# robot.net
KiCad netlist of a schematic drawn in EAGLE
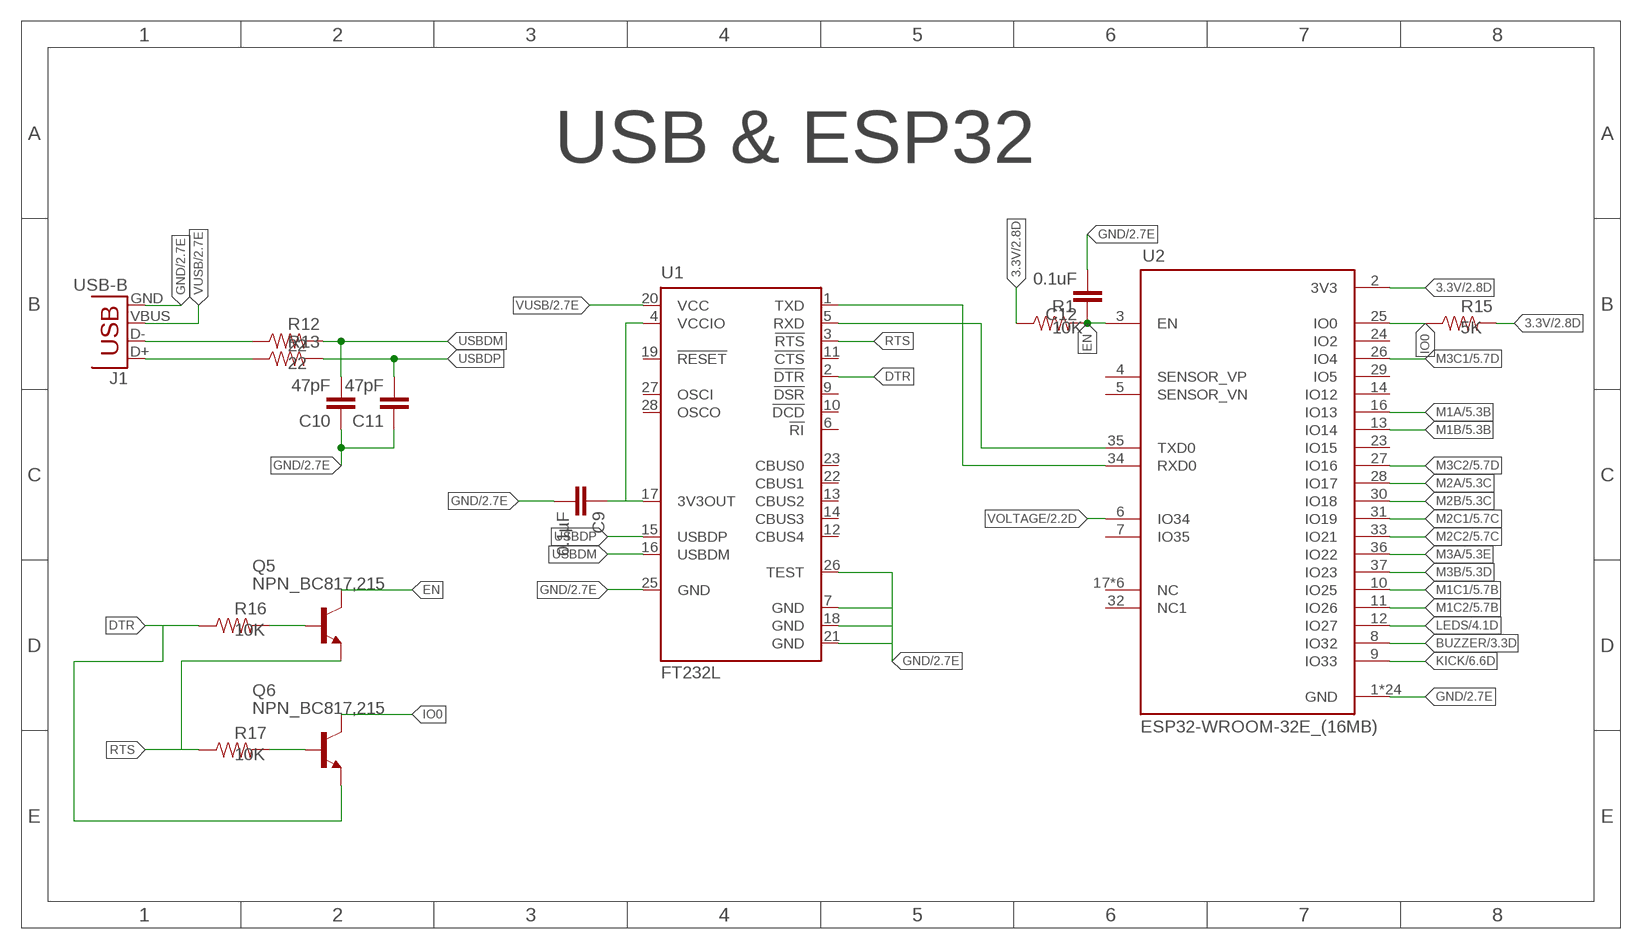
[diagram p0: schematic, sheet 1]
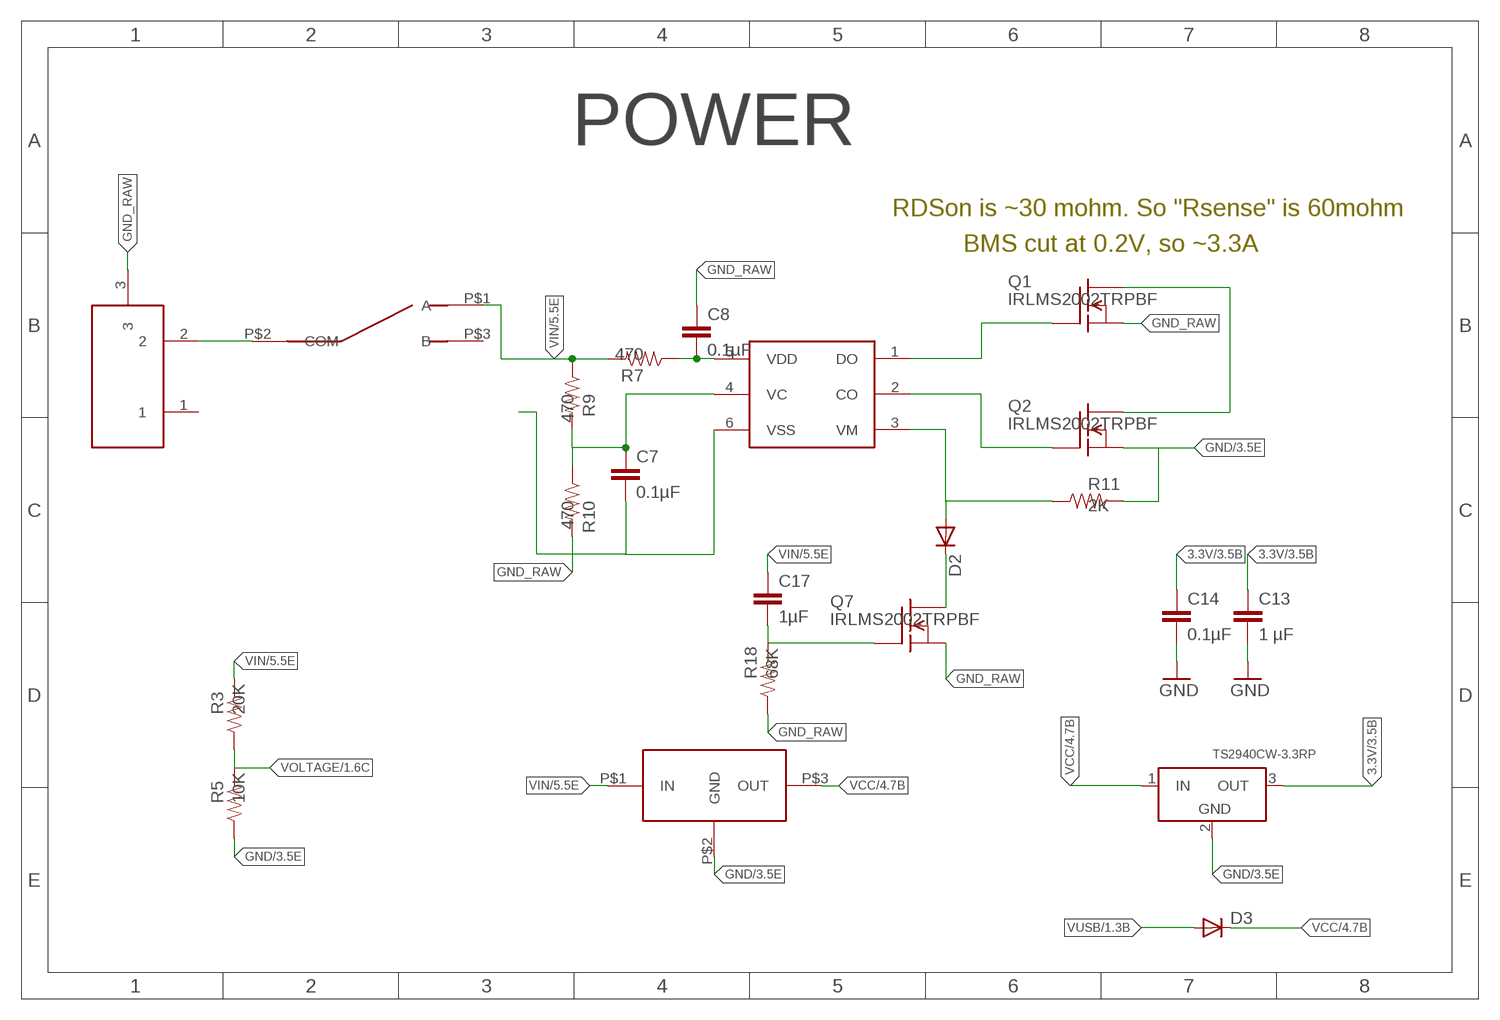
[diagram p1: schematic, sheet 2]
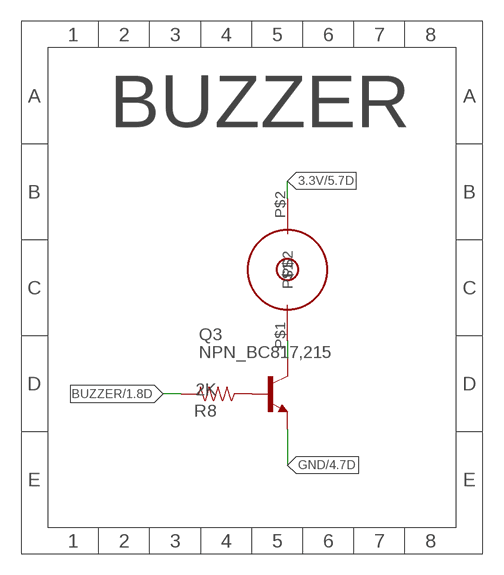
[diagram p2: schematic, sheet 3]
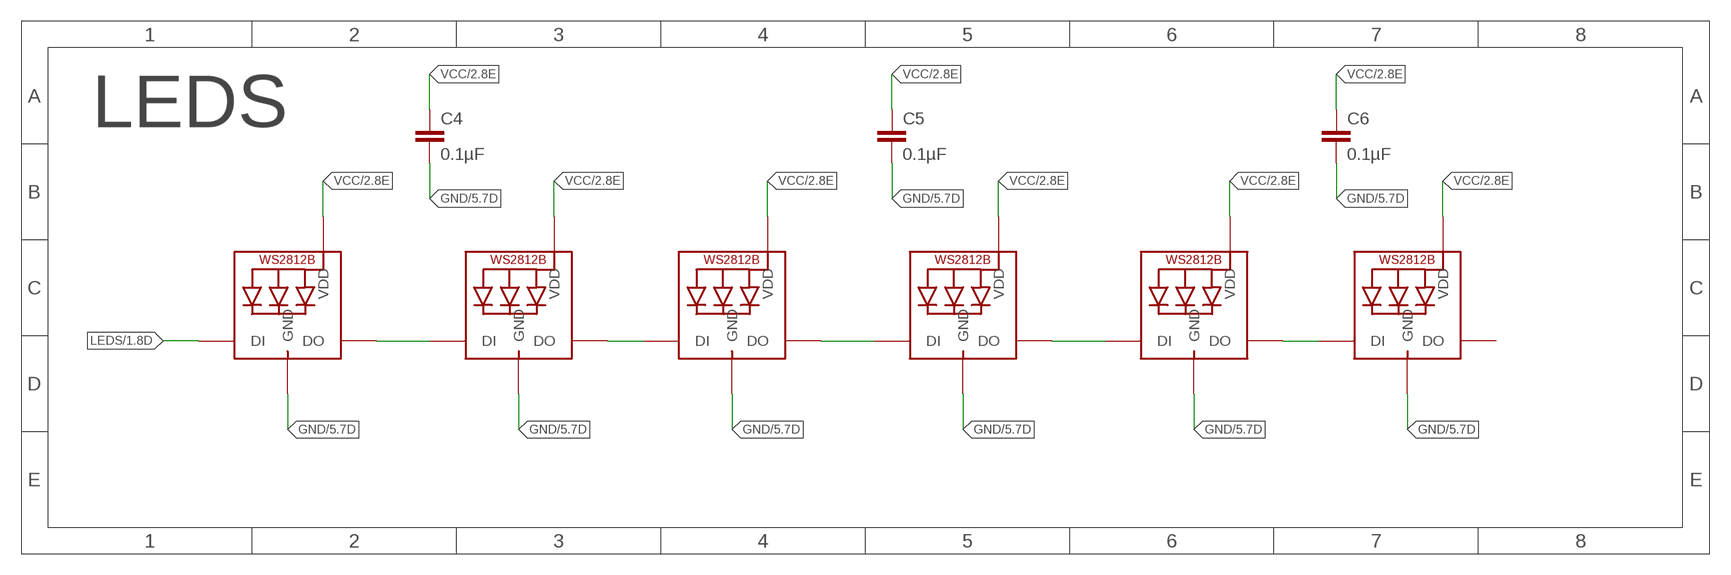
[diagram p3: schematic, sheet 4]
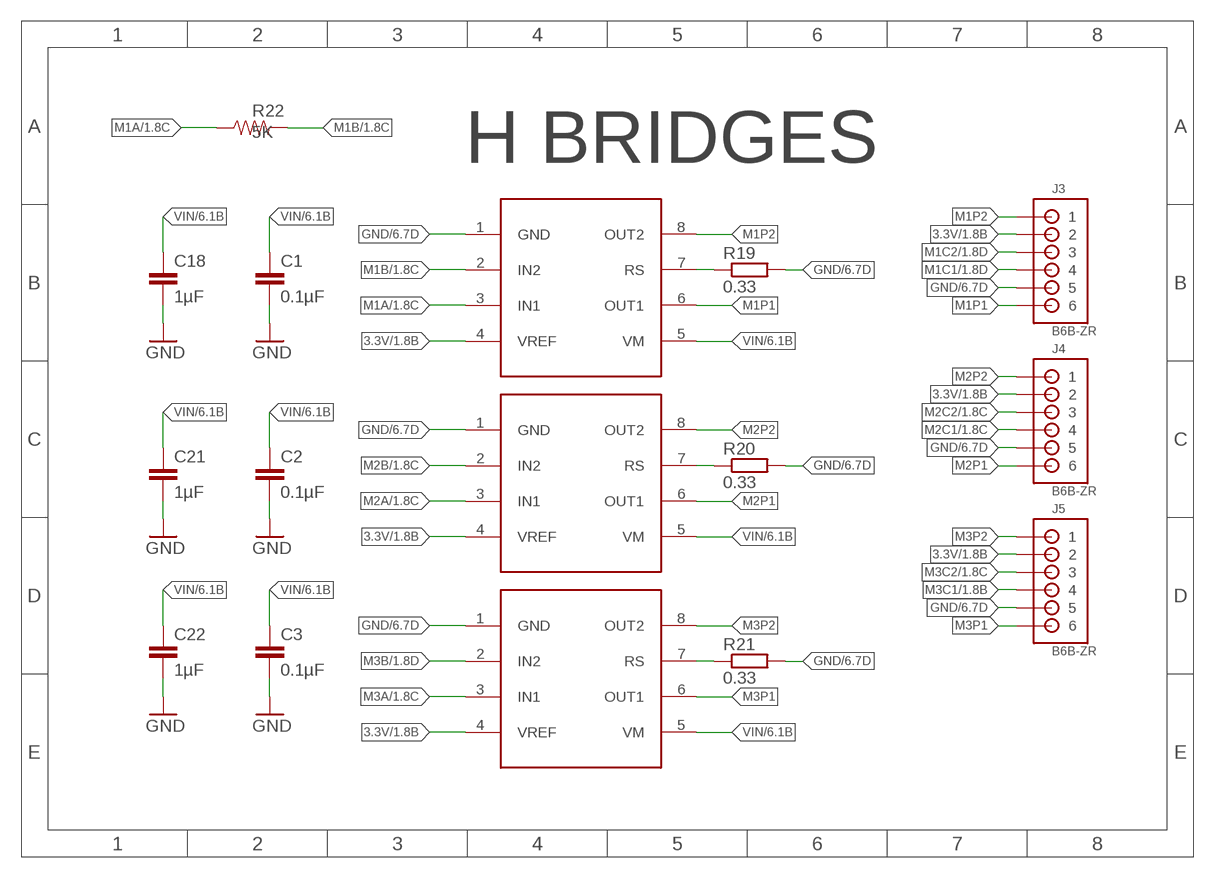
[diagram p4: schematic, sheet 5]
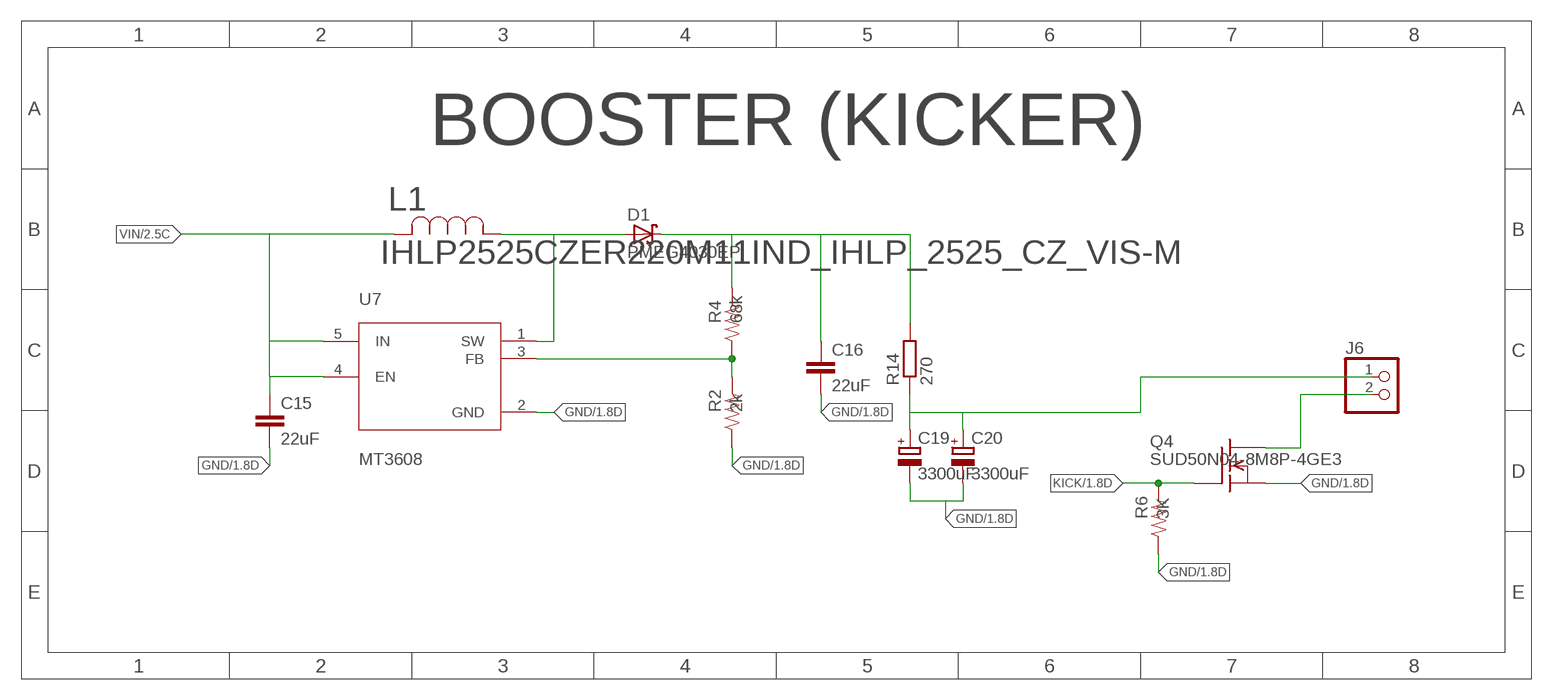
[diagram p5: schematic, sheet 6]

(export (version "E")
  (design (tool "Eeschema 10.0.6"))
  (components
    (comp (ref "C1")
      (value "0.1µF")
      (footprint "eagle-import:0805")
      (libsource (lib "eagle-import") (part "0.33UF/330NF-0805-50V-10%"))
    )
    (comp (ref "C2")
      (value "0.1µF")
      (footprint "eagle-import:0805")
      (fields (field (name "PROD_ID") "CAP-08469"))
      (libsource (lib "eagle-import") (part "0.33UF/330NF-0805-50V-10%"))
    )
    (comp (ref "C3")
      (value "0.1µF")
      (footprint "eagle-import:0805")
      (fields (field (name "PROD_ID") "CAP-08469"))
      (libsource (lib "eagle-import") (part "0.33UF/330NF-0805-50V-10%"))
    )
    (comp (ref "C18")
      (value "1µF")
      (footprint "eagle-import:0805")
      (libsource (lib "eagle-import") (part "0.33UF/330NF-0805-50V-10%"))
    )
    (comp (ref "C21")
      (value "1µF")
      (footprint "eagle-import:0805")
      (fields (field (name "PROD_ID") "CAP-08469"))
      (libsource (lib "eagle-import") (part "0.33UF/330NF-0805-50V-10%"))
    )
    (comp (ref "C22")
      (value "1µF")
      (footprint "eagle-import:0805")
      (fields (field (name "PROD_ID") "CAP-08469"))
      (libsource (lib "eagle-import") (part "0.33UF/330NF-0805-50V-10%"))
    )
    (comp (ref "J3")
      (value "B6B-ZR")
      (footprint "eagle-import:B6B-ZR")
      (libsource (lib "eagle-import") (part "B6B-ZR"))
    )
    (comp (ref "J4")
      (value "B6B-ZR")
      (footprint "eagle-import:B6B-ZR")
      (libsource (lib "eagle-import") (part "B6B-ZR"))
    )
    (comp (ref "J5")
      (value "B6B-ZR")
      (footprint "eagle-import:B6B-ZR")
      (libsource (lib "eagle-import") (part "B6B-ZR"))
    )
    (comp (ref "R19")
      (value "0.33")
      (footprint "eagle-import:R1206")
      (libsource (lib "eagle-import") (part "R-EU_R1206"))
    )
    (comp (ref "R20")
      (value "0.33")
      (footprint "eagle-import:R1206")
      (libsource (lib "eagle-import") (part "R-EU_R1206"))
    )
    (comp (ref "R21")
      (value "0.33")
      (footprint "eagle-import:R1206")
      (libsource (lib "eagle-import") (part "R-EU_R1206"))
    )
    (comp (ref "R22")
      (value "5K")
      (footprint "eagle-import:0805")
      (fields (field (name "PROD_ID") "RES-11622"))
      (libsource (lib "eagle-import") (part "0.3OHM-0805-1/8W-1%"))
    )
    (comp (ref "U10")
      (value "TB67H450FNG")
      (footprint "eagle-import:HSOP8")
      (libsource (lib "eagle-import") (part "TB67H450FNG"))
    )
    (comp (ref "U11")
      (value "TB67H450FNG")
      (footprint "eagle-import:HSOP8")
      (libsource (lib "eagle-import") (part "TB67H450FNG"))
    )
    (comp (ref "U12")
      (value "TB67H450FNG")
      (footprint "eagle-import:HSOP8")
      (libsource (lib "eagle-import") (part "TB67H450FNG"))
    )
    (comp (ref "B1")
      (value "BUZZER66")
      (footprint "eagle-import:BUZZER66")
      (libsource (lib "eagle-import") (part "BUZZER66"))
    )
    (comp (ref "Q3")
      (value "NPN_BC817,215")
      (footprint "eagle-import:SOT-23")
      (libsource (lib "eagle-import") (part "NPN_BC817,215"))
    )
    (comp (ref "R8")
      (value "2K")
      (footprint "eagle-import:0805")
      (libsource (lib "eagle-import") (part "0.3OHM-0805-1/8W-1%"))
    )
    (comp (ref "C4")
      (value "0.1µF")
      (footprint "eagle-import:0805")
      (libsource (lib "eagle-import") (part "0.33UF/330NF-0805-50V-10%"))
    )
    (comp (ref "C5")
      (value "0.1µF")
      (footprint "eagle-import:0805")
      (fields (field (name "PROD_ID") "CAP-08469"))
      (libsource (lib "eagle-import") (part "0.33UF/330NF-0805-50V-10%"))
    )
    (comp (ref "C6")
      (value "0.1µF")
      (footprint "eagle-import:0805")
      (fields (field (name "PROD_ID") "CAP-08469"))
      (libsource (lib "eagle-import") (part "0.33UF/330NF-0805-50V-10%"))
    )
    (comp (ref "LED1")
      (value "WS2812B5050")
      (footprint "eagle-import:WS2812B")
      (libsource (lib "eagle-import") (part "WS2812B5050"))
    )
    (comp (ref "LED2")
      (value "WS2812B5050")
      (footprint "eagle-import:WS2812B")
      (libsource (lib "eagle-import") (part "WS2812B5050"))
    )
    (comp (ref "LED3")
      (value "WS2812B5050")
      (footprint "eagle-import:WS2812B")
      (libsource (lib "eagle-import") (part "WS2812B5050"))
    )
    (comp (ref "LED4")
      (value "WS2812B5050")
      (footprint "eagle-import:WS2812B")
      (libsource (lib "eagle-import") (part "WS2812B5050"))
    )
    (comp (ref "LED5")
      (value "WS2812B5050")
      (footprint "eagle-import:WS2812B")
      (libsource (lib "eagle-import") (part "WS2812B5050"))
    )
    (comp (ref "LED6")
      (value "WS2812B5050")
      (footprint "eagle-import:WS2812B")
      (libsource (lib "eagle-import") (part "WS2812B5050"))
    )
    (comp (ref "C7")
      (value "0.1µF")
      (footprint "eagle-import:0805")
      (libsource (lib "eagle-import") (part "0.33UF/330NF-0805-50V-10%"))
    )
    (comp (ref "C8")
      (value "0.1µF")
      (footprint "eagle-import:0805")
      (fields (field (name "PROD_ID") "CAP-08469"))
      (libsource (lib "eagle-import") (part "0.33UF/330NF-0805-50V-10%"))
    )
    (comp (ref "C13")
      (value "1 µF")
      (footprint "eagle-import:0805")
      (fields (field (name "PROD_ID") "CAP-08469"))
      (libsource (lib "eagle-import") (part "0.33UF/330NF-0805-50V-10%"))
    )
    (comp (ref "C14")
      (value "0.1µF")
      (footprint "eagle-import:0805")
      (fields (field (name "PROD_ID") "CAP-08469"))
      (libsource (lib "eagle-import") (part "0.33UF/330NF-0805-50V-10%"))
    )
    (comp (ref "C17")
      (value "1µF")
      (footprint "eagle-import:0805")
      (fields (field (name "PROD_ID") "CAP-08469"))
      (libsource (lib "eagle-import") (part "0.33UF/330NF-0805-50V-10%"))
    )
    (comp (ref "D2")
      (value "DIODESOD")
      (footprint "eagle-import:SOD-323")
      (libsource (lib "eagle-import") (part "DIODESOD"))
    )
    (comp (ref "D3")
      (value "DIODESOD")
      (footprint "eagle-import:SOD-323")
      (libsource (lib "eagle-import") (part "DIODESOD"))
    )
    (comp (ref "J2")
      (value "DC21MMX")
      (footprint "eagle-import:DC-21MM")
      (libsource (lib "eagle-import") (part "DC21MMX"))
    )
    (comp (ref "Q1")
      (value "IRLMS2002TRPBF")
      (footprint "eagle-import:SOT23-6")
      (libsource (lib "eagle-import") (part "IRLMS2002TRPBF"))
    )
    (comp (ref "Q2")
      (value "IRLMS2002TRPBF")
      (footprint "eagle-import:SOT23-6")
      (libsource (lib "eagle-import") (part "IRLMS2002TRPBF"))
    )
    (comp (ref "Q7")
      (value "IRLMS2002TRPBF")
      (footprint "eagle-import:SOT23-6")
      (libsource (lib "eagle-import") (part "IRLMS2002TRPBF"))
    )
    (comp (ref "R3")
      (value "20K")
      (footprint "eagle-import:0805")
      (libsource (lib "eagle-import") (part "0.3OHM-0805-1/8W-1%"))
    )
    (comp (ref "R5")
      (value "10K")
      (footprint "eagle-import:0805")
      (libsource (lib "eagle-import") (part "0.3OHM-0805-1/8W-1%"))
    )
    (comp (ref "R7")
      (value "470")
      (footprint "eagle-import:0805")
      (libsource (lib "eagle-import") (part "0.3OHM-0805-1/8W-1%"))
    )
    (comp (ref "R9")
      (value "470")
      (footprint "eagle-import:0805")
      (libsource (lib "eagle-import") (part "0.3OHM-0805-1/8W-1%"))
    )
    (comp (ref "R10")
      (value "470")
      (footprint "eagle-import:0805")
      (libsource (lib "eagle-import") (part "0.3OHM-0805-1/8W-1%"))
    )
    (comp (ref "R11")
      (value "2K")
      (footprint "eagle-import:0805")
      (libsource (lib "eagle-import") (part "0.3OHM-0805-1/8W-1%"))
    )
    (comp (ref "R18")
      (value "68K")
      (footprint "eagle-import:0805")
      (fields (field (name "PROD_ID") "RES-11622"))
      (libsource (lib "eagle-import") (part "0.3OHM-0805-1/8W-1%"))
    )
    (comp (ref "REG1")
      (value "REG_5V")
      (footprint "eagle-import:TRACOPOWER")
      (libsource (lib "eagle-import") (part "REG_5V"))
    )
    (comp (ref "SW1")
      (value "L102011ML04Q")
      (footprint "eagle-import:L102011ML04Q")
      (libsource (lib "eagle-import") (part "L102011ML04Q"))
    )
    (comp (ref "U3")
      (value "S8252")
      (footprint "eagle-import:SOT23-6")
      (libsource (lib "eagle-import") (part "S8252"))
    )
    (comp (ref "U8")
      (value "TS2940CW-3.3RP")
      (footprint "eagle-import:SOT223")
      (libsource (lib "eagle-import") (part "TS2940CW-3.3RP"))
    )
    (comp (ref "C9")
      (value "0.1µF")
      (footprint "eagle-import:0805")
      (libsource (lib "eagle-import") (part "0.33UF/330NF-0805-50V-10%"))
    )
    (comp (ref "C10")
      (value "47pF")
      (footprint "eagle-import:0805")
      (libsource (lib "eagle-import") (part "CAP0805"))
    )
    (comp (ref "C11")
      (value "47pF")
      (footprint "eagle-import:0805")
      (libsource (lib "eagle-import") (part "CAP0805"))
    )
    (comp (ref "C12")
      (value "0.1uF")
      (footprint "eagle-import:0805")
      (libsource (lib "eagle-import") (part "CAP0805"))
    )
    (comp (ref "J1")
      (value "USB-B")
      (footprint "eagle-import:USB-B-PTH")
      (libsource (lib "eagle-import") (part "USBPTH"))
    )
    (comp (ref "Q5")
      (value "NPN_BC817,215")
      (footprint "eagle-import:SOT-23")
      (libsource (lib "eagle-import") (part "NPN_BC817,215"))
    )
    (comp (ref "Q6")
      (value "NPN_BC817,215")
      (footprint "eagle-import:SOT-23")
      (libsource (lib "eagle-import") (part "NPN_BC817,215"))
    )
    (comp (ref "R1")
      (value "10K")
      (footprint "eagle-import:0805")
      (fields (field (name "PROD_ID") "RES-11622"))
      (libsource (lib "eagle-import") (part "0.3OHM-0805-1/8W-1%"))
    )
    (comp (ref "R12")
      (value "22")
      (footprint "eagle-import:0805")
      (libsource (lib "eagle-import") (part "0.3OHM-0805-1/8W-1%"))
    )
    (comp (ref "R13")
      (value "22")
      (footprint "eagle-import:0805")
      (fields (field (name "PROD_ID") "RES-11622"))
      (libsource (lib "eagle-import") (part "0.3OHM-0805-1/8W-1%"))
    )
    (comp (ref "R15")
      (value "5K")
      (footprint "eagle-import:0805")
      (fields (field (name "PROD_ID") "RES-11622"))
      (libsource (lib "eagle-import") (part "0.3OHM-0805-1/8W-1%"))
    )
    (comp (ref "R16")
      (value "10K")
      (footprint "eagle-import:0805")
      (fields (field (name "PROD_ID") "RES-11622"))
      (libsource (lib "eagle-import") (part "0.3OHM-0805-1/8W-1%"))
    )
    (comp (ref "R17")
      (value "10K")
      (footprint "eagle-import:0805")
      (fields (field (name "PROD_ID") "RES-11622"))
      (libsource (lib "eagle-import") (part "0.3OHM-0805-1/8W-1%"))
    )
    (comp (ref "U1")
      (value "FT232L")
      (footprint "eagle-import:SSOP28")
      (fields (field (name "MPN") "FT232RL"))
      (libsource (lib "eagle-import") (part "FT232L"))
    )
    (comp (ref "U2")
      (value "ESP32-WROOM-32E_(16MB)")
      (footprint "eagle-import:MODULE_ESP32-WROOM-32E_(16MB)")
      (fields (field (name "MF") "Espressif Systems") (field (name "MP") "ESP32-WROOM-32E (16MB)"))
      (libsource (lib "eagle-import") (part "ESP32-WROOM-32E_(16MB)"))
    )
    (comp (ref "C15")
      (value "22uF")
      (footprint "eagle-import:C0805")
      (libsource (lib "eagle-import") (part "C-EUC0805"))
    )
    (comp (ref "C16")
      (value "22uF")
      (footprint "eagle-import:C0805")
      (libsource (lib "eagle-import") (part "C-EUC0805"))
    )
    (comp (ref "C19")
      (value "3300uF")
      (footprint "eagle-import:E5-13")
      (libsource (lib "eagle-import") (part "CPOL-EUE5-13"))
    )
    (comp (ref "C20")
      (value "3300uF")
      (footprint "eagle-import:E5-13")
      (libsource (lib "eagle-import") (part "CPOL-EUE5-13"))
    )
    (comp (ref "D1")
      (value "PMEG4030EP")
      (footprint "eagle-import:SOD128")
      (libsource (lib "eagle-import") (part "PMEG4030EP"))
    )
    (comp (ref "J6")
      (value "KICKER")
      (footprint "eagle-import:KICKER")
      (libsource (lib "eagle-import") (part "KICKER"))
    )
    (comp (ref "L1")
      (value "IHLP2525CZER220M11IND_IHLP_2525_CZ_VIS-M")
      (footprint "eagle-import:IND_IHLP_2525_CZ_VIS-M")
      (fields (field (name "MANUFACTURER_PART_NUMBER") "IHLP2525CZER220M11"))
      (libsource (lib "eagle-import") (part "IHLP2525CZER220M11IND_IHLP_2525_CZ_VIS-M"))
    )
    (comp (ref "Q4")
      (value "SUD50N04-8M8P-4GE3")
      (footprint "eagle-import:TO252")
      (libsource (lib "eagle-import") (part "SUD50N04-8M8P-4GE3"))
    )
    (comp (ref "R2")
      (value "2k")
      (footprint "eagle-import:0805")
      (libsource (lib "eagle-import") (part "0.3OHM-0805-1/8W-1%"))
    )
    (comp (ref "R4")
      (value "68k")
      (footprint "eagle-import:0805")
      (libsource (lib "eagle-import") (part "0.3OHM-0805-1/8W-1%"))
    )
    (comp (ref "R6")
      (value "3K")
      (footprint "eagle-import:0805")
      (fields (field (name "PROD_ID") "RES-11622"))
      (libsource (lib "eagle-import") (part "0.3OHM-0805-1/8W-1%"))
    )
    (comp (ref "R14")
      (value "270")
      (footprint "eagle-import:R2010")
      (libsource (lib "eagle-import") (part "R-EU_R2010"))
    )
    (comp (ref "U7")
      (value "MT3608")
      (footprint "eagle-import:SOT95P280X145-6N")
      (fields (field (name "MF") "Aerosemi Technology Co., Ltd"))
      (libsource (lib "eagle-import") (part "MT3608"))
    )
  )
  (nets
    (net (code "1") (name "1") (class "Default")
      (node (ref "J2") (pin "1") (pinfunction "1_1") (pintype "power_in"))
    )
    (net (code "2") (name "3.3V") (class "Default")
      (node (ref "B1") (pin "P$2") (pinfunction "P$2_P$2") (pintype "bidirectional"))
      (node (ref "C13") (pin "1") (pinfunction "1_1") (pintype "passive"))
      (node (ref "C14") (pin "1") (pinfunction "1_1") (pintype "passive"))
      (node (ref "J3") (pin "2") (pinfunction "2_2") (pintype "bidirectional"))
      (node (ref "J4") (pin "2") (pinfunction "2_2") (pintype "bidirectional"))
      (node (ref "J5") (pin "2") (pinfunction "2_2") (pintype "bidirectional"))
      (node (ref "R1") (pin "1") (pinfunction "1_1") (pintype "passive"))
      (node (ref "R15") (pin "2") (pinfunction "2_2") (pintype "passive"))
      (node (ref "U10") (pin "4") (pinfunction "VREF_4") (pintype "bidirectional"))
      (node (ref "U11") (pin "4") (pinfunction "VREF_4") (pintype "bidirectional"))
      (node (ref "U12") (pin "4") (pinfunction "VREF_4") (pintype "bidirectional"))
      (node (ref "U2") (pin "2") (pinfunction "3V3_2") (pintype "power_in"))
      (node (ref "U8") (pin "3") (pinfunction "OUT_3") (pintype "output"))
    )
    (net (code "3") (name "BUZZER") (class "Default")
      (node (ref "R8") (pin "2") (pinfunction "2_2") (pintype "passive"))
      (node (ref "U2") (pin "8") (pinfunction "IO32_8") (pintype "bidirectional"))
    )
    (net (code "4") (name "DTR") (class "Default")
      (node (ref "Q6") (pin "2") (pinfunction "E_2") (pintype "passive"))
      (node (ref "R16") (pin "1") (pinfunction "1_1") (pintype "passive"))
      (node (ref "U1") (pin "2") (pinfunction "~{DTR}_2") (pintype "output"))
    )
    (net (code "5") (name "EN") (class "Default")
      (node (ref "C12") (pin "1") (pinfunction "1_1") (pintype "passive"))
      (node (ref "Q5") (pin "3") (pinfunction "C_3") (pintype "passive"))
      (node (ref "R1") (pin "2") (pinfunction "2_2") (pintype "passive"))
      (node (ref "U2") (pin "3") (pinfunction "EN_3") (pintype "input"))
    )
    (net (code "6") (name "GND") (class "Default")
      (node (ref "C1") (pin "2") (pinfunction "2_2") (pintype "passive"))
      (node (ref "C10") (pin "1") (pinfunction "1_1") (pintype "passive"))
      (node (ref "C11") (pin "1") (pinfunction "1_1") (pintype "passive"))
      (node (ref "C12") (pin "2") (pinfunction "2_2") (pintype "passive"))
      (node (ref "C13") (pin "2") (pinfunction "2_2") (pintype "passive"))
      (node (ref "C14") (pin "2") (pinfunction "2_2") (pintype "passive"))
      (node (ref "C15") (pin "2") (pinfunction "2_2") (pintype "passive"))
      (node (ref "C16") (pin "2") (pinfunction "2_2") (pintype "passive"))
      (node (ref "C18") (pin "2") (pinfunction "2_2") (pintype "passive"))
      (node (ref "C19") (pin "-") (pinfunction "-_-") (pintype "passive"))
      (node (ref "C2") (pin "2") (pinfunction "2_2") (pintype "passive"))
      (node (ref "C20") (pin "-") (pinfunction "-_-") (pintype "passive"))
      (node (ref "C21") (pin "2") (pinfunction "2_2") (pintype "passive"))
      (node (ref "C22") (pin "2") (pinfunction "2_2") (pintype "passive"))
      (node (ref "C3") (pin "2") (pinfunction "2_2") (pintype "passive"))
      (node (ref "C4") (pin "2") (pinfunction "2_2") (pintype "passive"))
      (node (ref "C5") (pin "2") (pinfunction "2_2") (pintype "passive"))
      (node (ref "C6") (pin "2") (pinfunction "2_2") (pintype "passive"))
      (node (ref "C9") (pin "2") (pinfunction "2_2") (pintype "passive"))
      (node (ref "J1") (pin "GND") (pinfunction "GND_GND") (pintype "bidirectional"))
      (node (ref "J3") (pin "5") (pinfunction "5_5") (pintype "bidirectional"))
      (node (ref "J4") (pin "5") (pinfunction "5_5") (pintype "bidirectional"))
      (node (ref "J5") (pin "5") (pinfunction "5_5") (pintype "bidirectional"))
      (node (ref "LED1") (pin "3-GND") (pinfunction "GND_3-GND") (pintype "power_in"))
      (node (ref "LED2") (pin "3-GND") (pinfunction "GND_3-GND") (pintype "power_in"))
      (node (ref "LED3") (pin "3-GND") (pinfunction "GND_3-GND") (pintype "power_in"))
      (node (ref "LED4") (pin "3-GND") (pinfunction "GND_3-GND") (pintype "power_in"))
      (node (ref "LED5") (pin "3-GND") (pinfunction "GND_3-GND") (pintype "power_in"))
      (node (ref "LED6") (pin "3-GND") (pinfunction "GND_3-GND") (pintype "power_in"))
      (node (ref "Q2") (pin "4") (pinfunction "S_4") (pintype "passive"))
      (node (ref "Q3") (pin "2") (pinfunction "E_2") (pintype "passive"))
      (node (ref "Q4") (pin "2") (pinfunction "S_2") (pintype "passive"))
      (node (ref "R11") (pin "2") (pinfunction "2_2") (pintype "passive"))
      (node (ref "R19") (pin "2") (pinfunction "2_2") (pintype "passive"))
      (node (ref "R2") (pin "1") (pinfunction "1_1") (pintype "passive"))
      (node (ref "R20") (pin "2") (pinfunction "2_2") (pintype "passive"))
      (node (ref "R21") (pin "2") (pinfunction "2_2") (pintype "passive"))
      (node (ref "R5") (pin "1") (pinfunction "1_1") (pintype "passive"))
      (node (ref "R6") (pin "1") (pinfunction "1_1") (pintype "passive"))
      (node (ref "REG1") (pin "P$2") (pinfunction "GND_P$2") (pintype "bidirectional"))
      (node (ref "U1") (pin "18") (pinfunction "GND_18") (pintype "power_in"))
      (node (ref "U1") (pin "21") (pinfunction "GND_21") (pintype "power_in"))
      (node (ref "U1") (pin "25") (pinfunction "GND_25") (pintype "power_in"))
      (node (ref "U1") (pin "26") (pinfunction "TEST_26") (pintype "input"))
      (node (ref "U1") (pin "7") (pinfunction "GND_7") (pintype "power_in"))
      (node (ref "U10") (pin "1") (pinfunction "GND_1") (pintype "bidirectional"))
      (node (ref "U11") (pin "1") (pinfunction "GND_1") (pintype "bidirectional"))
      (node (ref "U12") (pin "1") (pinfunction "GND_1") (pintype "bidirectional"))
      (node (ref "U2") (pin "1") (pinfunction "GND_1") (pintype "power_in"))
      (node (ref "U2") (pin "15") (pinfunction "GND_15") (pintype "power_in"))
      (node (ref "U2") (pin "38") (pinfunction "GND_38") (pintype "power_in"))
      (node (ref "U2") (pin "39_1") (pinfunction "GND_39_1") (pintype "power_in"))
      (node (ref "U2") (pin "39_10") (pinfunction "GND_39_10") (pintype "power_in"))
      (node (ref "U2") (pin "39_11") (pinfunction "GND_39_11") (pintype "power_in"))
      (node (ref "U2") (pin "39_12") (pinfunction "GND_39_12") (pintype "power_in"))
      (node (ref "U2") (pin "39_13") (pinfunction "GND_39_13") (pintype "power_in"))
      (node (ref "U2") (pin "39_14") (pinfunction "GND_39_14") (pintype "power_in"))
      (node (ref "U2") (pin "39_15") (pinfunction "GND_39_15") (pintype "power_in"))
      (node (ref "U2") (pin "39_16") (pinfunction "GND_39_16") (pintype "power_in"))
      (node (ref "U2") (pin "39_17") (pinfunction "GND_39_17") (pintype "power_in"))
      (node (ref "U2") (pin "39_18") (pinfunction "GND_39_18") (pintype "power_in"))
      (node (ref "U2") (pin "39_19") (pinfunction "GND_39_19") (pintype "power_in"))
      (node (ref "U2") (pin "39_2") (pinfunction "GND_39_2") (pintype "power_in"))
      (node (ref "U2") (pin "39_20") (pinfunction "GND_39_20") (pintype "power_in"))
      (node (ref "U2") (pin "39_21") (pinfunction "GND_39_21") (pintype "power_in"))
      (node (ref "U2") (pin "39_3") (pinfunction "GND_39_3") (pintype "power_in"))
      (node (ref "U2") (pin "39_4") (pinfunction "GND_39_4") (pintype "power_in"))
      (node (ref "U2") (pin "39_5") (pinfunction "GND_39_5") (pintype "power_in"))
      (node (ref "U2") (pin "39_6") (pinfunction "GND_39_6") (pintype "power_in"))
      (node (ref "U2") (pin "39_7") (pinfunction "GND_39_7") (pintype "power_in"))
      (node (ref "U2") (pin "39_8") (pinfunction "GND_39_8") (pintype "power_in"))
      (node (ref "U2") (pin "39_9") (pinfunction "GND_39_9") (pintype "power_in"))
      (node (ref "U7") (pin "2") (pinfunction "GND_2") (pintype "power_in"))
      (node (ref "U8") (pin "2") (pinfunction "GND_2") (pintype "power_in"))
    )
    (net (code "7") (name "GND_RAW") (class "Default")
      (node (ref "C7") (pin "2") (pinfunction "2_2") (pintype "passive"))
      (node (ref "C8") (pin "1") (pinfunction "1_1") (pintype "passive"))
      (node (ref "J2") (pin "3") (pinfunction "3_3") (pintype "power_in"))
      (node (ref "Q1") (pin "4") (pinfunction "S_4") (pintype "passive"))
      (node (ref "Q7") (pin "4") (pinfunction "S_4") (pintype "passive"))
      (node (ref "R10") (pin "2") (pinfunction "2_2") (pintype "passive"))
      (node (ref "R18") (pin "1") (pinfunction "1_1") (pintype "passive"))
      (node (ref "U3") (pin "6") (pinfunction "VSS_6") (pintype "passive"))
    )
    (net (code "8") (name "IO0") (class "Default")
      (node (ref "Q6") (pin "3") (pinfunction "C_3") (pintype "passive"))
      (node (ref "R15") (pin "1") (pinfunction "1_1") (pintype "passive"))
      (node (ref "U2") (pin "25") (pinfunction "IO0_25") (pintype "bidirectional"))
    )
    (net (code "9") (name "KICK") (class "Default")
      (node (ref "Q4") (pin "1") (pinfunction "G_1") (pintype "passive"))
      (node (ref "R6") (pin "2") (pinfunction "2_2") (pintype "passive"))
      (node (ref "U2") (pin "9") (pinfunction "IO33_9") (pintype "bidirectional"))
    )
    (net (code "10") (name "LEDS") (class "Default")
      (node (ref "LED1") (pin "4-DIN") (pinfunction "DI_4-DIN") (pintype "input"))
      (node (ref "U2") (pin "12") (pinfunction "IO27_12") (pintype "bidirectional"))
    )
    (net (code "11") (name "M1A") (class "Default")
      (node (ref "R22") (pin "1") (pinfunction "1_1") (pintype "passive"))
      (node (ref "U10") (pin "3") (pinfunction "IN1_3") (pintype "bidirectional"))
      (node (ref "U2") (pin "16") (pinfunction "IO13_16") (pintype "bidirectional"))
    )
    (net (code "12") (name "M1B") (class "Default")
      (node (ref "R22") (pin "2") (pinfunction "2_2") (pintype "passive"))
      (node (ref "U10") (pin "2") (pinfunction "IN2_2") (pintype "bidirectional"))
      (node (ref "U2") (pin "13") (pinfunction "IO14_13") (pintype "bidirectional"))
    )
    (net (code "13") (name "M1C1") (class "Default")
      (node (ref "J3") (pin "4") (pinfunction "4_4") (pintype "bidirectional"))
      (node (ref "U2") (pin "10") (pinfunction "IO25_10") (pintype "bidirectional"))
    )
    (net (code "14") (name "M1C2") (class "Default")
      (node (ref "J3") (pin "3") (pinfunction "3_3") (pintype "bidirectional"))
      (node (ref "U2") (pin "11") (pinfunction "IO26_11") (pintype "bidirectional"))
    )
    (net (code "15") (name "M1P1") (class "Default")
      (node (ref "J3") (pin "6") (pinfunction "6_6") (pintype "bidirectional"))
      (node (ref "U10") (pin "6") (pinfunction "OUT1_6") (pintype "bidirectional"))
    )
    (net (code "16") (name "M1P2") (class "Default")
      (node (ref "J3") (pin "1") (pinfunction "1_1") (pintype "bidirectional"))
      (node (ref "U10") (pin "8") (pinfunction "OUT2_8") (pintype "bidirectional"))
    )
    (net (code "17") (name "M2A") (class "Default")
      (node (ref "U11") (pin "3") (pinfunction "IN1_3") (pintype "bidirectional"))
      (node (ref "U2") (pin "28") (pinfunction "IO17_28") (pintype "bidirectional"))
    )
    (net (code "18") (name "M2B") (class "Default")
      (node (ref "U11") (pin "2") (pinfunction "IN2_2") (pintype "bidirectional"))
      (node (ref "U2") (pin "30") (pinfunction "IO18_30") (pintype "bidirectional"))
    )
    (net (code "19") (name "M2C1") (class "Default")
      (node (ref "J4") (pin "4") (pinfunction "4_4") (pintype "bidirectional"))
      (node (ref "U2") (pin "31") (pinfunction "IO19_31") (pintype "bidirectional"))
    )
    (net (code "20") (name "M2C2") (class "Default")
      (node (ref "J4") (pin "3") (pinfunction "3_3") (pintype "bidirectional"))
      (node (ref "U2") (pin "33") (pinfunction "IO21_33") (pintype "bidirectional"))
    )
    (net (code "21") (name "M2P1") (class "Default")
      (node (ref "J4") (pin "6") (pinfunction "6_6") (pintype "bidirectional"))
      (node (ref "U11") (pin "6") (pinfunction "OUT1_6") (pintype "bidirectional"))
    )
    (net (code "22") (name "M2P2") (class "Default")
      (node (ref "J4") (pin "1") (pinfunction "1_1") (pintype "bidirectional"))
      (node (ref "U11") (pin "8") (pinfunction "OUT2_8") (pintype "bidirectional"))
    )
    (net (code "23") (name "M3A") (class "Default")
      (node (ref "U12") (pin "3") (pinfunction "IN1_3") (pintype "bidirectional"))
      (node (ref "U2") (pin "36") (pinfunction "IO22_36") (pintype "bidirectional"))
    )
    (net (code "24") (name "M3B") (class "Default")
      (node (ref "U12") (pin "2") (pinfunction "IN2_2") (pintype "bidirectional"))
      (node (ref "U2") (pin "37") (pinfunction "IO23_37") (pintype "bidirectional"))
    )
    (net (code "25") (name "M3C1") (class "Default")
      (node (ref "J5") (pin "4") (pinfunction "4_4") (pintype "bidirectional"))
      (node (ref "U2") (pin "26") (pinfunction "IO4_26") (pintype "bidirectional"))
    )
    (net (code "26") (name "M3C2") (class "Default")
      (node (ref "J5") (pin "3") (pinfunction "3_3") (pintype "bidirectional"))
      (node (ref "U2") (pin "27") (pinfunction "IO16_27") (pintype "bidirectional"))
    )
    (net (code "27") (name "M3P1") (class "Default")
      (node (ref "J5") (pin "6") (pinfunction "6_6") (pintype "bidirectional"))
      (node (ref "U12") (pin "6") (pinfunction "OUT1_6") (pintype "bidirectional"))
    )
    (net (code "28") (name "M3P2") (class "Default")
      (node (ref "J5") (pin "1") (pinfunction "1_1") (pintype "bidirectional"))
      (node (ref "U12") (pin "8") (pinfunction "OUT2_8") (pintype "bidirectional"))
    )
    (net (code "29") (name "Net-(C19-Pad+)") (class "Default")
      (node (ref "C19") (pin "+") (pinfunction "+_+") (pintype "passive"))
      (node (ref "C20") (pin "+") (pinfunction "+_+") (pintype "passive"))
      (node (ref "J6") (pin "1") (pinfunction "1_1") (pintype "passive"))
      (node (ref "R14") (pin "1") (pinfunction "1_1") (pintype "passive"))
    )
    (net (code "30") (name "Net-(D1-A)") (class "Default")
      (node (ref "D1") (pin "2") (pinfunction "A_2") (pintype "passive"))
      (node (ref "L1") (pin "1") (pinfunction "1_1") (pintype "passive"))
      (node (ref "U7") (pin "1") (pinfunction "SW_1") (pintype "output"))
    )
    (net (code "31") (name "Net-(D1-K)") (class "Default")
      (node (ref "C16") (pin "1") (pinfunction "1_1") (pintype "passive"))
      (node (ref "D1") (pin "1") (pinfunction "K_1") (pintype "passive"))
      (node (ref "R14") (pin "2") (pinfunction "2_2") (pintype "passive"))
      (node (ref "R4") (pin "2") (pinfunction "2_2") (pintype "passive"))
    )
    (net (code "32") (name "Net-(D2-A)") (class "Default")
      (node (ref "D2") (pin "2") (pinfunction "A_2") (pintype "passive"))
      (node (ref "R11") (pin "1") (pinfunction "1_1") (pintype "passive"))
      (node (ref "U3") (pin "3") (pinfunction "VM_3") (pintype "passive"))
    )
    (net (code "33") (name "Net-(D2-C)") (class "Default")
      (node (ref "D2") (pin "1") (pinfunction "C_1") (pintype "passive"))
      (node (ref "Q7") (pin "1") (pinfunction "D_1") (pintype "passive"))
      (node (ref "Q7") (pin "2") (pinfunction "D_2") (pintype "passive"))
      (node (ref "Q7") (pin "5") (pinfunction "D_5") (pintype "passive"))
      (node (ref "Q7") (pin "6") (pinfunction "D_6") (pintype "passive"))
    )
    (net (code "34") (name "Net-(J1-PadD+)") (class "Default")
      (node (ref "J1") (pin "D+") (pinfunction "D+_D+") (pintype "bidirectional"))
      (node (ref "R13") (pin "1") (pinfunction "1_1") (pintype "passive"))
    )
    (net (code "35") (name "Net-(J1-PadD-)") (class "Default")
      (node (ref "J1") (pin "D-") (pinfunction "D-_D-") (pintype "bidirectional"))
      (node (ref "R12") (pin "1") (pinfunction "1_1") (pintype "passive"))
    )
    (net (code "36") (name "Net-(LED1-DO)") (class "Default")
      (node (ref "LED1") (pin "2-DOUT") (pinfunction "DO_2-DOUT") (pintype "output"))
      (node (ref "LED2") (pin "4-DIN") (pinfunction "DI_4-DIN") (pintype "input"))
    )
    (net (code "37") (name "Net-(LED2-DO)") (class "Default")
      (node (ref "LED2") (pin "2-DOUT") (pinfunction "DO_2-DOUT") (pintype "output"))
      (node (ref "LED3") (pin "4-DIN") (pinfunction "DI_4-DIN") (pintype "input"))
    )
    (net (code "38") (name "Net-(LED3-DO)") (class "Default")
      (node (ref "LED3") (pin "2-DOUT") (pinfunction "DO_2-DOUT") (pintype "output"))
      (node (ref "LED4") (pin "4-DIN") (pinfunction "DI_4-DIN") (pintype "input"))
    )
    (net (code "39") (name "Net-(LED4-DO)") (class "Default")
      (node (ref "LED4") (pin "2-DOUT") (pinfunction "DO_2-DOUT") (pintype "output"))
      (node (ref "LED5") (pin "4-DIN") (pinfunction "DI_4-DIN") (pintype "input"))
    )
    (net (code "40") (name "Net-(LED5-DO)") (class "Default")
      (node (ref "LED5") (pin "2-DOUT") (pinfunction "DO_2-DOUT") (pintype "output"))
      (node (ref "LED6") (pin "4-DIN") (pinfunction "DI_4-DIN") (pintype "input"))
    )
    (net (code "41") (name "Net-(Q1-D-Pad1)") (class "Default")
      (node (ref "Q1") (pin "1") (pinfunction "D_1") (pintype "passive"))
      (node (ref "Q1") (pin "2") (pinfunction "D_2") (pintype "passive"))
      (node (ref "Q1") (pin "5") (pinfunction "D_5") (pintype "passive"))
      (node (ref "Q1") (pin "6") (pinfunction "D_6") (pintype "passive"))
      (node (ref "Q2") (pin "1") (pinfunction "D_1") (pintype "passive"))
      (node (ref "Q2") (pin "2") (pinfunction "D_2") (pintype "passive"))
      (node (ref "Q2") (pin "5") (pinfunction "D_5") (pintype "passive"))
      (node (ref "Q2") (pin "6") (pinfunction "D_6") (pintype "passive"))
    )
    (net (code "42") (name "Net-(Q1-G)") (class "Default")
      (node (ref "Q1") (pin "3") (pinfunction "G_3") (pintype "passive"))
      (node (ref "U3") (pin "1") (pinfunction "DO_1") (pintype "passive"))
    )
    (net (code "43") (name "Net-(Q2-G)") (class "Default")
      (node (ref "Q2") (pin "3") (pinfunction "G_3") (pintype "passive"))
      (node (ref "U3") (pin "2") (pinfunction "CO_2") (pintype "passive"))
    )
    (net (code "44") (name "Net-(Q3-B)") (class "Default")
      (node (ref "Q3") (pin "1") (pinfunction "B_1") (pintype "passive"))
      (node (ref "R8") (pin "1") (pinfunction "1_1") (pintype "passive"))
    )
    (net (code "45") (name "Net-(Q3-C)") (class "Default")
      (node (ref "B1") (pin "P$1") (pinfunction "P$1_P$1") (pintype "bidirectional"))
      (node (ref "Q3") (pin "3") (pinfunction "C_3") (pintype "passive"))
    )
    (net (code "46") (name "Net-(Q4-D)") (class "Default")
      (node (ref "J6") (pin "2") (pinfunction "2_2") (pintype "passive"))
      (node (ref "Q4") (pin "3") (pinfunction "D_3") (pintype "passive"))
    )
    (net (code "47") (name "Net-(Q5-B)") (class "Default")
      (node (ref "Q5") (pin "1") (pinfunction "B_1") (pintype "passive"))
      (node (ref "R16") (pin "2") (pinfunction "2_2") (pintype "passive"))
    )
    (net (code "48") (name "Net-(Q6-B)") (class "Default")
      (node (ref "Q6") (pin "1") (pinfunction "B_1") (pintype "passive"))
      (node (ref "R17") (pin "2") (pinfunction "2_2") (pintype "passive"))
    )
    (net (code "49") (name "Net-(Q7-G)") (class "Default")
      (node (ref "C17") (pin "2") (pinfunction "2_2") (pintype "passive"))
      (node (ref "Q7") (pin "3") (pinfunction "G_3") (pintype "passive"))
      (node (ref "R18") (pin "2") (pinfunction "2_2") (pintype "passive"))
    )
    (net (code "50") (name "Net-(SW1-COM)") (class "Default")
      (node (ref "J2") (pin "2") (pinfunction "2_2") (pintype "power_in"))
      (node (ref "SW1") (pin "P$2") (pinfunction "COM_P$2") (pintype "bidirectional"))
    )
    (net (code "51") (name "Net-(U1-3V3OUT)") (class "Default")
      (node (ref "C9") (pin "1") (pinfunction "1_1") (pintype "passive"))
      (node (ref "U1") (pin "17") (pinfunction "3V3OUT_17") (pintype "output"))
      (node (ref "U1") (pin "4") (pinfunction "VCCIO_4") (pintype "power_in"))
    )
    (net (code "52") (name "Net-(U1-RXD)") (class "Default")
      (node (ref "U1") (pin "5") (pinfunction "RXD_5") (pintype "input"))
      (node (ref "U2") (pin "35") (pinfunction "TXD0_35") (pintype "bidirectional"))
    )
    (net (code "53") (name "Net-(U1-TXD)") (class "Default")
      (node (ref "U1") (pin "1") (pinfunction "TXD_1") (pintype "output"))
      (node (ref "U2") (pin "34") (pinfunction "RXD0_34") (pintype "bidirectional"))
    )
    (net (code "54") (name "Net-(U3-VC)") (class "Default")
      (node (ref "C7") (pin "1") (pinfunction "1_1") (pintype "passive"))
      (node (ref "R10") (pin "1") (pinfunction "1_1") (pintype "passive"))
      (node (ref "R9") (pin "2") (pinfunction "2_2") (pintype "passive"))
      (node (ref "U3") (pin "4") (pinfunction "VC_4") (pintype "passive"))
    )
    (net (code "55") (name "Net-(U3-VDD)") (class "Default")
      (node (ref "C8") (pin "2") (pinfunction "2_2") (pintype "passive"))
      (node (ref "R7") (pin "1") (pinfunction "1_1") (pintype "passive"))
      (node (ref "U3") (pin "5") (pinfunction "VDD_5") (pintype "passive"))
    )
    (net (code "56") (name "Net-(U7-FB)") (class "Default")
      (node (ref "R2") (pin "2") (pinfunction "2_2") (pintype "passive"))
      (node (ref "R4") (pin "1") (pinfunction "1_1") (pintype "passive"))
      (node (ref "U7") (pin "3") (pinfunction "FB_3") (pintype "input"))
    )
    (net (code "57") (name "Net-(U10-RS)") (class "Default")
      (node (ref "R19") (pin "1") (pinfunction "1_1") (pintype "passive"))
      (node (ref "U10") (pin "7") (pinfunction "RS_7") (pintype "bidirectional"))
    )
    (net (code "58") (name "Net-(U11-RS)") (class "Default")
      (node (ref "R20") (pin "1") (pinfunction "1_1") (pintype "passive"))
      (node (ref "U11") (pin "7") (pinfunction "RS_7") (pintype "bidirectional"))
    )
    (net (code "59") (name "Net-(U12-RS)") (class "Default")
      (node (ref "R21") (pin "1") (pinfunction "1_1") (pintype "passive"))
      (node (ref "U12") (pin "7") (pinfunction "RS_7") (pintype "bidirectional"))
    )
    (net (code "60") (name "RTS") (class "Default")
      (node (ref "Q5") (pin "2") (pinfunction "E_2") (pintype "passive"))
      (node (ref "R17") (pin "1") (pinfunction "1_1") (pintype "passive"))
      (node (ref "U1") (pin "3") (pinfunction "~{RTS}_3") (pintype "output"))
    )
    (net (code "61") (name "USBDM") (class "Default")
      (node (ref "C10") (pin "2") (pinfunction "2_2") (pintype "passive"))
      (node (ref "R12") (pin "2") (pinfunction "2_2") (pintype "passive"))
      (node (ref "U1") (pin "16") (pinfunction "USBDM_16") (pintype "bidirectional"))
    )
    (net (code "62") (name "USBDP") (class "Default")
      (node (ref "C11") (pin "2") (pinfunction "2_2") (pintype "passive"))
      (node (ref "R13") (pin "2") (pinfunction "2_2") (pintype "passive"))
      (node (ref "U1") (pin "15") (pinfunction "USBDP_15") (pintype "bidirectional"))
    )
    (net (code "63") (name "VCC") (class "Default")
      (node (ref "C4") (pin "1") (pinfunction "1_1") (pintype "passive"))
      (node (ref "C5") (pin "1") (pinfunction "1_1") (pintype "passive"))
      (node (ref "C6") (pin "1") (pinfunction "1_1") (pintype "passive"))
      (node (ref "D3") (pin "1") (pinfunction "C_1") (pintype "passive"))
      (node (ref "LED1") (pin "1-VDD") (pinfunction "VDD_1-VDD") (pintype "power_in"))
      (node (ref "LED2") (pin "1-VDD") (pinfunction "VDD_1-VDD") (pintype "power_in"))
      (node (ref "LED3") (pin "1-VDD") (pinfunction "VDD_1-VDD") (pintype "power_in"))
      (node (ref "LED4") (pin "1-VDD") (pinfunction "VDD_1-VDD") (pintype "power_in"))
      (node (ref "LED5") (pin "1-VDD") (pinfunction "VDD_1-VDD") (pintype "power_in"))
      (node (ref "LED6") (pin "1-VDD") (pinfunction "VDD_1-VDD") (pintype "power_in"))
      (node (ref "REG1") (pin "P$3") (pinfunction "OUT_P$3") (pintype "bidirectional"))
      (node (ref "U8") (pin "1") (pinfunction "IN_1") (pintype "input"))
    )
    (net (code "64") (name "VIN") (class "Default")
      (node (ref "C1") (pin "1") (pinfunction "1_1") (pintype "passive"))
      (node (ref "C15") (pin "1") (pinfunction "1_1") (pintype "passive"))
      (node (ref "C17") (pin "1") (pinfunction "1_1") (pintype "passive"))
      (node (ref "C18") (pin "1") (pinfunction "1_1") (pintype "passive"))
      (node (ref "C2") (pin "1") (pinfunction "1_1") (pintype "passive"))
      (node (ref "C21") (pin "1") (pinfunction "1_1") (pintype "passive"))
      (node (ref "C22") (pin "1") (pinfunction "1_1") (pintype "passive"))
      (node (ref "C3") (pin "1") (pinfunction "1_1") (pintype "passive"))
      (node (ref "L1") (pin "2") (pinfunction "2_2") (pintype "passive"))
      (node (ref "R3") (pin "2") (pinfunction "2_2") (pintype "passive"))
      (node (ref "R7") (pin "2") (pinfunction "2_2") (pintype "passive"))
      (node (ref "R9") (pin "1") (pinfunction "1_1") (pintype "passive"))
      (node (ref "REG1") (pin "P$1") (pinfunction "IN_P$1") (pintype "bidirectional"))
      (node (ref "SW1") (pin "P$1") (pinfunction "A_P$1") (pintype "bidirectional"))
      (node (ref "U10") (pin "5") (pinfunction "VM_5") (pintype "bidirectional"))
      (node (ref "U11") (pin "5") (pinfunction "VM_5") (pintype "bidirectional"))
      (node (ref "U12") (pin "5") (pinfunction "VM_5") (pintype "bidirectional"))
      (node (ref "U7") (pin "4") (pinfunction "EN_4") (pintype "input"))
      (node (ref "U7") (pin "5") (pinfunction "IN_5") (pintype "input"))
    )
    (net (code "65") (name "VOLTAGE") (class "Default")
      (node (ref "R3") (pin "1") (pinfunction "1_1") (pintype "passive"))
      (node (ref "R5") (pin "2") (pinfunction "2_2") (pintype "passive"))
      (node (ref "U2") (pin "6") (pinfunction "IO34_6") (pintype "input"))
    )
    (net (code "66") (name "VUSB") (class "Default")
      (node (ref "D3") (pin "2") (pinfunction "A_2") (pintype "passive"))
      (node (ref "J1") (pin "VBUS") (pinfunction "VBUS_VBUS") (pintype "bidirectional"))
      (node (ref "U1") (pin "20") (pinfunction "VCC_20") (pintype "power_in"))
    )
    (net (code "67") (name "unconnected-(LED6-DO-Pad2-DOUT)") (class "Default")
      (node (ref "LED6") (pin "2-DOUT") (pinfunction "DO_2-DOUT") (pintype "output"))
    )
    (net (code "68") (name "unconnected-(SW1-B-PadP$3)") (class "Default")
      (node (ref "SW1") (pin "P$3") (pinfunction "B_P$3") (pintype "bidirectional"))
    )
    (net (code "69") (name "unconnected-(U1-CBUS0-Pad23)") (class "Default")
      (node (ref "U1") (pin "23") (pinfunction "CBUS0_23") (pintype "bidirectional"))
    )
    (net (code "70") (name "unconnected-(U1-CBUS1-Pad22)") (class "Default")
      (node (ref "U1") (pin "22") (pinfunction "CBUS1_22") (pintype "bidirectional"))
    )
    (net (code "71") (name "unconnected-(U1-CBUS2-Pad13)") (class "Default")
      (node (ref "U1") (pin "13") (pinfunction "CBUS2_13") (pintype "bidirectional"))
    )
    (net (code "72") (name "unconnected-(U1-CBUS3-Pad14)") (class "Default")
      (node (ref "U1") (pin "14") (pinfunction "CBUS3_14") (pintype "bidirectional"))
    )
    (net (code "73") (name "unconnected-(U1-CBUS4-Pad12)") (class "Default")
      (node (ref "U1") (pin "12") (pinfunction "CBUS4_12") (pintype "bidirectional"))
    )
    (net (code "74") (name "unconnected-(U1-OSCI-Pad27)") (class "Default")
      (node (ref "U1") (pin "27") (pinfunction "OSCI_27") (pintype "input"))
    )
    (net (code "75") (name "unconnected-(U1-OSCO-Pad28)") (class "Default")
      (node (ref "U1") (pin "28") (pinfunction "OSCO_28") (pintype "output"))
    )
    (net (code "76") (name "unconnected-(U1-~{CTS}-Pad11)") (class "Default")
      (node (ref "U1") (pin "11") (pinfunction "~{CTS}_11") (pintype "input"))
    )
    (net (code "77") (name "unconnected-(U1-~{DCD}-Pad10)") (class "Default")
      (node (ref "U1") (pin "10") (pinfunction "~{DCD}_10") (pintype "input"))
    )
    (net (code "78") (name "unconnected-(U1-~{DSR}-Pad9)") (class "Default")
      (node (ref "U1") (pin "9") (pinfunction "~{DSR}_9") (pintype "input"))
    )
    (net (code "79") (name "unconnected-(U1-~{RESET}-Pad19)") (class "Default")
      (node (ref "U1") (pin "19") (pinfunction "~{RESET}_19") (pintype "input"))
    )
    (net (code "80") (name "unconnected-(U1-~{RI}-Pad6)") (class "Default")
      (node (ref "U1") (pin "6") (pinfunction "~{RI}_6") (pintype "input"))
    )
    (net (code "81") (name "unconnected-(U2-IO2-Pad24)") (class "Default")
      (node (ref "U2") (pin "24") (pinfunction "IO2_24") (pintype "bidirectional"))
    )
    (net (code "82") (name "unconnected-(U2-IO5-Pad29)") (class "Default")
      (node (ref "U2") (pin "29") (pinfunction "IO5_29") (pintype "bidirectional"))
    )
    (net (code "83") (name "unconnected-(U2-IO12-Pad14)") (class "Default")
      (node (ref "U2") (pin "14") (pinfunction "IO12_14") (pintype "bidirectional"))
    )
    (net (code "84") (name "unconnected-(U2-IO15-Pad23)") (class "Default")
      (node (ref "U2") (pin "23") (pinfunction "IO15_23") (pintype "bidirectional"))
    )
    (net (code "85") (name "unconnected-(U2-IO35-Pad7)") (class "Default")
      (node (ref "U2") (pin "7") (pinfunction "IO35_7") (pintype "input"))
    )
    (net (code "86") (name "unconnected-(U2-NC-Pad17)") (class "Default")
      (node (ref "U2") (pin "17") (pinfunction "NC_17") (pintype "no_connect"))
    )
    (net (code "87") (name "unconnected-(U2-NC-Pad18)") (class "Default")
      (node (ref "U2") (pin "18") (pinfunction "NC_18") (pintype "no_connect"))
    )
    (net (code "88") (name "unconnected-(U2-NC-Pad19)") (class "Default")
      (node (ref "U2") (pin "19") (pinfunction "NC_19") (pintype "no_connect"))
    )
    (net (code "89") (name "unconnected-(U2-NC-Pad20)") (class "Default")
      (node (ref "U2") (pin "20") (pinfunction "NC_20") (pintype "no_connect"))
    )
    (net (code "90") (name "unconnected-(U2-NC-Pad21)") (class "Default")
      (node (ref "U2") (pin "21") (pinfunction "NC_21") (pintype "no_connect"))
    )
    (net (code "91") (name "unconnected-(U2-NC-Pad22)") (class "Default")
      (node (ref "U2") (pin "22") (pinfunction "NC_22") (pintype "no_connect"))
    )
    (net (code "92") (name "unconnected-(U2-NC1-Pad32)") (class "Default")
      (node (ref "U2") (pin "32") (pinfunction "NC1_32") (pintype "no_connect"))
    )
    (net (code "93") (name "unconnected-(U2-SENSOR_VN-Pad5)") (class "Default")
      (node (ref "U2") (pin "5") (pinfunction "SENSOR_VN_5") (pintype "input"))
    )
    (net (code "94") (name "unconnected-(U2-SENSOR_VP-Pad4)") (class "Default")
      (node (ref "U2") (pin "4") (pinfunction "SENSOR_VP_4") (pintype "input"))
    )
  )
)
